# ESC.net
KiCad netlist of a schematic drawn in Altium Designer
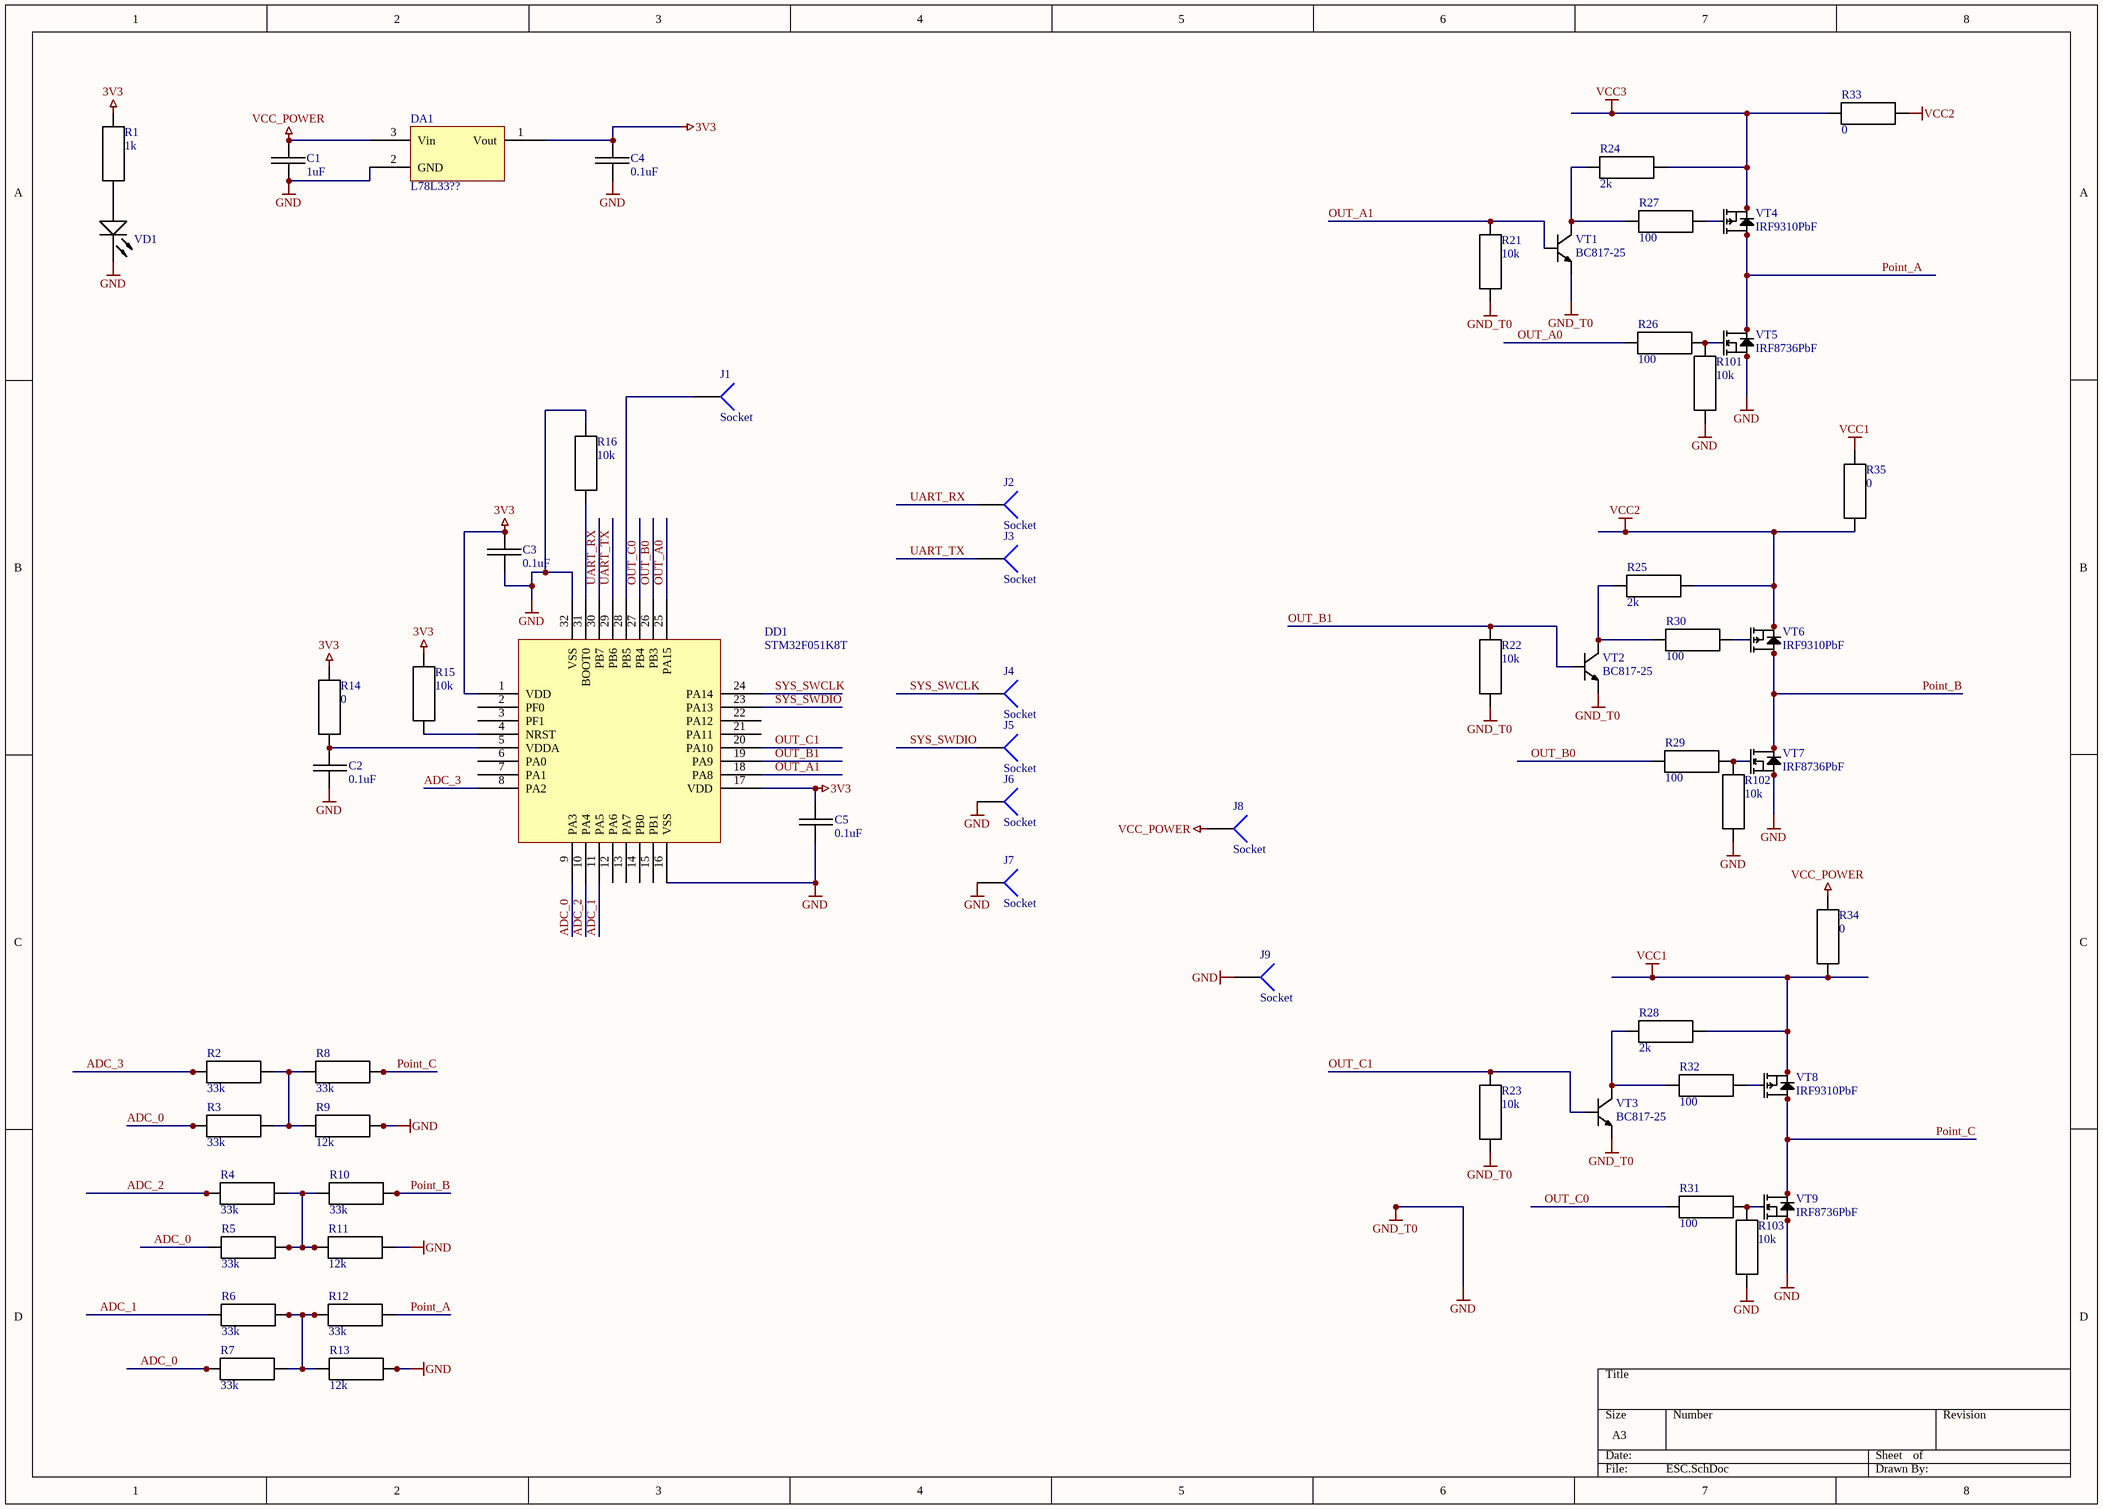
[diagram p0: ESC.SchDoc]

(export (version "E")
  (design (tool "Eeschema 10.0.6"))
  (components
    (comp (ref "C1")
      (value "1uF")
      (footprint "CAP0805")
      (fields (field (name "VOLTAGE") "50V"))
      (libsource (lib "Schlib1") (part "Capacitor"))
    )
    (comp (ref "C2")
      (value "0.1uF")
      (footprint "CAP0603")
      (fields (field (name "VOLTAGE") "50V"))
      (libsource (lib "Schlib1") (part "Capacitor"))
    )
    (comp (ref "C3")
      (value "0.1uF")
      (footprint "CAP0603")
      (fields (field (name "VOLTAGE") "50V"))
      (libsource (lib "Schlib1") (part "Capacitor"))
    )
    (comp (ref "C4")
      (value "0.1uF")
      (footprint "CAP0603")
      (fields (field (name "VOLTAGE") "50V"))
      (libsource (lib "Schlib1") (part "Capacitor"))
    )
    (comp (ref "C5")
      (value "0.1uF")
      (footprint "CAP0603")
      (fields (field (name "VOLTAGE") "50V"))
      (libsource (lib "Schlib1") (part "Capacitor"))
    )
    (comp (ref "DA1")
      (value "L78L33??")
      (footprint "SOT89")
      (description "LDO")
      (libsource (lib "Schlib1") (part "DA-L78L05"))
    )
    (comp (ref "DD1")
      (value "STM32F051K8T")
      (footprint "LQFP32-STM32")
      (description "LQFP32")
      (libsource (lib "Schlib1") (part "STM32F051K8T"))
    )
    (comp (ref "J1")
      (value "Socket")
      (footprint "PIN1")
      (fields (field (name "PUBLISHER") "Altium Limited"))
      (libsource (lib "Miscellaneous Connectors") (part "Socket"))
    )
    (comp (ref "J2")
      (value "Socket")
      (footprint "PIN1")
      (fields (field (name "PUBLISHER") "Altium Limited"))
      (libsource (lib "Miscellaneous Connectors") (part "Socket"))
    )
    (comp (ref "J3")
      (value "Socket")
      (footprint "PIN1")
      (fields (field (name "PUBLISHER") "Altium Limited"))
      (libsource (lib "Miscellaneous Connectors") (part "Socket"))
    )
    (comp (ref "J4")
      (value "Socket")
      (footprint "PIN1")
      (fields (field (name "PUBLISHER") "Altium Limited"))
      (libsource (lib "Miscellaneous Connectors") (part "Socket"))
    )
    (comp (ref "J5")
      (value "Socket")
      (footprint "PIN1")
      (fields (field (name "PUBLISHER") "Altium Limited"))
      (libsource (lib "Miscellaneous Connectors") (part "Socket"))
    )
    (comp (ref "J6")
      (value "Socket")
      (footprint "PIN1")
      (fields (field (name "PUBLISHER") "Altium Limited"))
      (libsource (lib "Miscellaneous Connectors") (part "Socket"))
    )
    (comp (ref "J7")
      (value "Socket")
      (footprint "PIN1")
      (fields (field (name "PUBLISHER") "Altium Limited"))
      (libsource (lib "Miscellaneous Connectors") (part "Socket"))
    )
    (comp (ref "J8")
      (value "Socket")
      (footprint "PIN1")
      (fields (field (name "PUBLISHER") "Altium Limited"))
      (libsource (lib "Miscellaneous Connectors") (part "Socket"))
    )
    (comp (ref "J9")
      (value "Socket")
      (footprint "PIN1")
      (fields (field (name "PUBLISHER") "Altium Limited"))
      (libsource (lib "Miscellaneous Connectors") (part "Socket"))
    )
    (comp (ref "R1") (value "1k") (footprint "RES0603") (libsource (lib "") (part "Resistor_2")))
    (comp (ref "R2") (value "33k") (footprint "RES0805") (libsource (lib "Schlib1") (part "Resistor")))
    (comp (ref "R3") (value "33k") (footprint "RES0805") (libsource (lib "Schlib1") (part "Resistor")))
    (comp (ref "R4") (value "33k") (footprint "RES0805") (libsource (lib "Schlib1") (part "Resistor")))
    (comp (ref "R5") (value "33k") (footprint "RES0805") (libsource (lib "Schlib1") (part "Resistor")))
    (comp (ref "R6") (value "33k") (footprint "RES0805") (libsource (lib "Schlib1") (part "Resistor")))
    (comp (ref "R7") (value "33k") (footprint "RES0805") (libsource (lib "Schlib1") (part "Resistor")))
    (comp (ref "R8") (value "33k") (footprint "RES0805") (libsource (lib "Schlib1") (part "Resistor")))
    (comp (ref "R9") (value "12k") (footprint "RES0805") (libsource (lib "Schlib1") (part "Resistor")))
    (comp (ref "R10") (value "33k") (footprint "RES0805") (libsource (lib "Schlib1") (part "Resistor")))
    (comp (ref "R11") (value "12k") (footprint "RES0805") (libsource (lib "Schlib1") (part "Resistor")))
    (comp (ref "R12") (value "33k") (footprint "RES0805") (libsource (lib "Schlib1") (part "Resistor")))
    (comp (ref "R13") (value "12k") (footprint "RES0805") (libsource (lib "Schlib1") (part "Resistor")))
    (comp (ref "R14") (value "0") (footprint "RES0603") (libsource (lib "") (part "Resistor_1")))
    (comp (ref "R15") (value "10k") (footprint "RES0603") (libsource (lib "") (part "Resistor_1")))
    (comp (ref "R16") (value "10k") (footprint "RES0603") (libsource (lib "") (part "Resistor_1")))
    (comp (ref "R21") (value "10k") (footprint "RES0603") (libsource (lib "") (part "Resistor_2")))
    (comp (ref "R22") (value "10k") (footprint "RES0603") (libsource (lib "") (part "Resistor_2")))
    (comp (ref "R23") (value "10k") (footprint "RES0603") (libsource (lib "") (part "Resistor_2")))
    (comp (ref "R24") (value "2k") (footprint "RES0603") (libsource (lib "Schlib1") (part "Resistor")))
    (comp (ref "R25") (value "2k") (footprint "RES0603") (libsource (lib "Schlib1") (part "Resistor")))
    (comp (ref "R26") (value "100") (footprint "RES0805") (libsource (lib "") (part "Resistor_3")))
    (comp (ref "R27") (value "100") (footprint "RES0603") (libsource (lib "") (part "Resistor_3")))
    (comp (ref "R28") (value "2k") (footprint "RES0603") (libsource (lib "Schlib1") (part "Resistor")))
    (comp (ref "R29") (value "100") (footprint "RES0805") (libsource (lib "") (part "Resistor_3")))
    (comp (ref "R30") (value "100") (footprint "RES0603") (libsource (lib "") (part "Resistor_3")))
    (comp (ref "R31") (value "100") (footprint "RES0805") (libsource (lib "") (part "Resistor_3")))
    (comp (ref "R32") (value "100") (footprint "RES0603") (libsource (lib "") (part "Resistor_3")))
    (comp (ref "R33") (value "0") (footprint "RES1206") (libsource (lib "") (part "Resistor_3")))
    (comp (ref "R34") (value "0") (footprint "RES2512") (libsource (lib "") (part "Resistor_1")))
    (comp (ref "R35") (value "0") (footprint "RES1206") (libsource (lib "") (part "Resistor_2")))
    (comp (ref "R101") (value "10k") (footprint "RES0603") (libsource (lib "") (part "Resistor_2")))
    (comp (ref "R102") (value "10k") (footprint "RES0603") (libsource (lib "") (part "Resistor_2")))
    (comp (ref "R103") (value "10k") (footprint "RES0603") (libsource (lib "") (part "Resistor_2")))
    (comp (ref "VD1")
      (value "KP-1608SURC")
      (footprint "Diode 1608")
      (libsource (lib "Schlib1") (part "LED_0603"))
    )
    (comp (ref "VT1")
      (value "BC817-25")
      (footprint "SOT23")
      (description "NPN")
      (libsource (lib "Schlib1") (part "VT - BC817"))
    )
    (comp (ref "VT2")
      (value "BC817-25")
      (footprint "SOT23")
      (description "NPN")
      (libsource (lib "Schlib1") (part "VT - BC817"))
    )
    (comp (ref "VT3")
      (value "BC817-25")
      (footprint "SOT23")
      (description "NPN")
      (libsource (lib "Schlib1") (part "VT - BC817"))
    )
    (comp (ref "VT4")
      (value "IRF9310PbF")
      (footprint "SO-8 IRF...")
      (description "P-MOSFET -20A")
      (libsource (lib "Schlib1") (part "IRF9310PbF"))
    )
    (comp (ref "VT5")
      (value "IRF8736PbF")
      (footprint "SO-8 IRF...")
      (description "N-MOSFET 18A")
      (libsource (lib "Schlib1") (part "IRF8736PbF"))
    )
    (comp (ref "VT6")
      (value "IRF9310PbF")
      (footprint "SO-8 IRF...")
      (description "P-MOSFET -20A")
      (libsource (lib "Schlib1") (part "IRF9310PbF"))
    )
    (comp (ref "VT7")
      (value "IRF8736PbF")
      (footprint "SO-8 IRF...")
      (description "N-MOSFET 18A")
      (libsource (lib "Schlib1") (part "IRF8736PbF"))
    )
    (comp (ref "VT8")
      (value "IRF9310PbF")
      (footprint "SO-8 IRF...")
      (description "P-MOSFET -20A")
      (libsource (lib "Schlib1") (part "IRF9310PbF"))
    )
    (comp (ref "VT9")
      (value "IRF8736PbF")
      (footprint "SO-8 IRF...")
      (description "N-MOSFET 18A")
      (libsource (lib "Schlib1") (part "IRF8736PbF"))
    )
  )
  (nets
    (net (code "1") (name "/ADC_0") (class "Default")
      (node (ref "DD1") (pin "9") (pinfunction "PA3_9") (pintype "passive"))
      (node (ref "R3") (pin "2") (pinfunction "2_2") (pintype "passive"))
      (node (ref "R5") (pin "2") (pinfunction "2_2") (pintype "passive"))
      (node (ref "R7") (pin "2") (pinfunction "2_2") (pintype "passive"))
    )
    (net (code "2") (name "/ADC_1") (class "Default")
      (node (ref "DD1") (pin "11") (pinfunction "PA5_11") (pintype "passive"))
      (node (ref "R6") (pin "2") (pinfunction "2_2") (pintype "passive"))
    )
    (net (code "3") (name "/ADC_2") (class "Default")
      (node (ref "DD1") (pin "10") (pinfunction "PA4_10") (pintype "passive"))
      (node (ref "R4") (pin "2") (pinfunction "2_2") (pintype "passive"))
    )
    (net (code "4") (name "/ADC_3") (class "Default")
      (node (ref "DD1") (pin "8") (pinfunction "PA2_8") (pintype "passive"))
      (node (ref "R2") (pin "2") (pinfunction "2_2") (pintype "passive"))
    )
    (net (code "5") (name "/OUT_A0") (class "Default")
      (node (ref "DD1") (pin "25") (pinfunction "PA15_25") (pintype "passive"))
      (node (ref "R26") (pin "1") (pinfunction "1_1") (pintype "passive"))
    )
    (net (code "6") (name "/OUT_A1") (class "Default")
      (node (ref "DD1") (pin "18") (pinfunction "PA8_18") (pintype "passive"))
      (node (ref "R21") (pin "1") (pinfunction "1_1") (pintype "passive"))
      (node (ref "VT1") (pin "1") (pinfunction "1_1") (pintype "passive"))
    )
    (net (code "7") (name "/OUT_B0") (class "Default")
      (node (ref "DD1") (pin "26") (pinfunction "PB3_26") (pintype "passive"))
      (node (ref "R29") (pin "1") (pinfunction "1_1") (pintype "passive"))
    )
    (net (code "8") (name "/OUT_B1") (class "Default")
      (node (ref "DD1") (pin "19") (pinfunction "PA9_19") (pintype "passive"))
      (node (ref "R22") (pin "1") (pinfunction "1_1") (pintype "passive"))
      (node (ref "VT2") (pin "1") (pinfunction "1_1") (pintype "passive"))
    )
    (net (code "9") (name "/OUT_C0") (class "Default")
      (node (ref "DD1") (pin "27") (pinfunction "PB4_27") (pintype "passive"))
      (node (ref "R31") (pin "1") (pinfunction "1_1") (pintype "passive"))
    )
    (net (code "10") (name "/OUT_C1") (class "Default")
      (node (ref "DD1") (pin "20") (pinfunction "PA10_20") (pintype "passive"))
      (node (ref "R23") (pin "1") (pinfunction "1_1") (pintype "passive"))
      (node (ref "VT3") (pin "1") (pinfunction "1_1") (pintype "passive"))
    )
    (net (code "11") (name "/Point_A") (class "Default")
      (node (ref "R12") (pin "1") (pinfunction "1_1") (pintype "passive"))
      (node (ref "VT4") (pin "5") (pinfunction "D_5") (pintype "passive"))
      (node (ref "VT4") (pin "6") (pinfunction "D_6") (pintype "passive"))
      (node (ref "VT4") (pin "7") (pinfunction "D_7") (pintype "passive"))
      (node (ref "VT4") (pin "8") (pinfunction "D_8") (pintype "passive"))
      (node (ref "VT5") (pin "5") (pinfunction "D_5") (pintype "passive"))
      (node (ref "VT5") (pin "6") (pinfunction "D_6") (pintype "passive"))
      (node (ref "VT5") (pin "7") (pinfunction "D_7") (pintype "passive"))
      (node (ref "VT5") (pin "8") (pinfunction "D_8") (pintype "passive"))
    )
    (net (code "12") (name "/Point_B") (class "Default")
      (node (ref "R10") (pin "1") (pinfunction "1_1") (pintype "passive"))
      (node (ref "VT6") (pin "5") (pinfunction "D_5") (pintype "passive"))
      (node (ref "VT6") (pin "6") (pinfunction "D_6") (pintype "passive"))
      (node (ref "VT6") (pin "7") (pinfunction "D_7") (pintype "passive"))
      (node (ref "VT6") (pin "8") (pinfunction "D_8") (pintype "passive"))
      (node (ref "VT7") (pin "5") (pinfunction "D_5") (pintype "passive"))
      (node (ref "VT7") (pin "6") (pinfunction "D_6") (pintype "passive"))
      (node (ref "VT7") (pin "7") (pinfunction "D_7") (pintype "passive"))
      (node (ref "VT7") (pin "8") (pinfunction "D_8") (pintype "passive"))
    )
    (net (code "13") (name "/Point_C") (class "Default")
      (node (ref "R8") (pin "1") (pinfunction "1_1") (pintype "passive"))
      (node (ref "VT8") (pin "5") (pinfunction "D_5") (pintype "passive"))
      (node (ref "VT8") (pin "6") (pinfunction "D_6") (pintype "passive"))
      (node (ref "VT8") (pin "7") (pinfunction "D_7") (pintype "passive"))
      (node (ref "VT8") (pin "8") (pinfunction "D_8") (pintype "passive"))
      (node (ref "VT9") (pin "5") (pinfunction "D_5") (pintype "passive"))
      (node (ref "VT9") (pin "6") (pinfunction "D_6") (pintype "passive"))
      (node (ref "VT9") (pin "7") (pinfunction "D_7") (pintype "passive"))
      (node (ref "VT9") (pin "8") (pinfunction "D_8") (pintype "passive"))
    )
    (net (code "14") (name "/SYS_SWCLK") (class "Default")
      (node (ref "DD1") (pin "24") (pinfunction "PA14_24") (pintype "passive"))
      (node (ref "J4") (pin "1") (pinfunction "1_1") (pintype "passive"))
    )
    (net (code "15") (name "/SYS_SWDIO") (class "Default")
      (node (ref "DD1") (pin "23") (pinfunction "PA13_23") (pintype "passive"))
      (node (ref "J5") (pin "1") (pinfunction "1_1") (pintype "passive"))
    )
    (net (code "16") (name "/UART_RX") (class "Default")
      (node (ref "DD1") (pin "30") (pinfunction "PB7_30") (pintype "passive"))
      (node (ref "J2") (pin "1") (pinfunction "1_1") (pintype "passive"))
    )
    (net (code "17") (name "/UART_TX") (class "Default")
      (node (ref "DD1") (pin "29") (pinfunction "PB6_29") (pintype "passive"))
      (node (ref "J3") (pin "1") (pinfunction "1_1") (pintype "passive"))
    )
    (net (code "18") (name "3V3") (class "Default")
      (node (ref "C3") (pin "1") (pinfunction "1_1") (pintype "passive"))
      (node (ref "C4") (pin "1") (pinfunction "1_1") (pintype "passive"))
      (node (ref "C5") (pin "2") (pinfunction "2_2") (pintype "passive"))
      (node (ref "DA1") (pin "1") (pinfunction "Vout_1") (pintype "passive"))
      (node (ref "DD1") (pin "1") (pinfunction "VDD_1") (pintype "passive"))
      (node (ref "DD1") (pin "17") (pinfunction "VDD_17") (pintype "passive"))
      (node (ref "R1") (pin "1") (pinfunction "1_1") (pintype "passive"))
      (node (ref "R14") (pin "2") (pinfunction "2_2") (pintype "passive"))
      (node (ref "R15") (pin "2") (pinfunction "2_2") (pintype "passive"))
    )
    (net (code "19") (name "GND") (class "Default")
      (node (ref "C1") (pin "2") (pinfunction "2_2") (pintype "passive"))
      (node (ref "C2") (pin "1") (pinfunction "1_1") (pintype "passive"))
      (node (ref "C3") (pin "2") (pinfunction "2_2") (pintype "passive"))
      (node (ref "C4") (pin "2") (pinfunction "2_2") (pintype "passive"))
      (node (ref "C5") (pin "1") (pinfunction "1_1") (pintype "passive"))
      (node (ref "DA1") (pin "2") (pinfunction "GND_2") (pintype "passive"))
      (node (ref "DD1") (pin "16") (pinfunction "VSS_16") (pintype "passive"))
      (node (ref "DD1") (pin "32") (pinfunction "VSS_32") (pintype "passive"))
      (node (ref "J6") (pin "1") (pinfunction "1_1") (pintype "passive"))
      (node (ref "J7") (pin "1") (pinfunction "1_1") (pintype "passive"))
      (node (ref "J9") (pin "1") (pinfunction "1_1") (pintype "passive"))
      (node (ref "R101") (pin "2") (pinfunction "2_2") (pintype "passive"))
      (node (ref "R102") (pin "2") (pinfunction "2_2") (pintype "passive"))
      (node (ref "R103") (pin "2") (pinfunction "2_2") (pintype "passive"))
      (node (ref "R11") (pin "1") (pinfunction "1_1") (pintype "passive"))
      (node (ref "R13") (pin "1") (pinfunction "1_1") (pintype "passive"))
      (node (ref "R16") (pin "2") (pinfunction "2_2") (pintype "passive"))
      (node (ref "R21") (pin "2") (pinfunction "2_2") (pintype "passive"))
      (node (ref "R22") (pin "2") (pinfunction "2_2") (pintype "passive"))
      (node (ref "R23") (pin "2") (pinfunction "2_2") (pintype "passive"))
      (node (ref "R9") (pin "1") (pinfunction "1_1") (pintype "passive"))
      (node (ref "VD1") (pin "1") (pinfunction "1_1") (pintype "passive"))
      (node (ref "VT1") (pin "2") (pinfunction "2_2") (pintype "passive"))
      (node (ref "VT2") (pin "2") (pinfunction "2_2") (pintype "passive"))
      (node (ref "VT3") (pin "2") (pinfunction "2_2") (pintype "passive"))
      (node (ref "VT5") (pin "1") (pinfunction "S_1") (pintype "passive"))
      (node (ref "VT5") (pin "2") (pinfunction "S_2") (pintype "passive"))
      (node (ref "VT5") (pin "3") (pinfunction "S_3") (pintype "passive"))
      (node (ref "VT7") (pin "1") (pinfunction "S_1") (pintype "passive"))
      (node (ref "VT7") (pin "2") (pinfunction "S_2") (pintype "passive"))
      (node (ref "VT7") (pin "3") (pinfunction "S_3") (pintype "passive"))
      (node (ref "VT9") (pin "1") (pinfunction "S_1") (pintype "passive"))
      (node (ref "VT9") (pin "2") (pinfunction "S_2") (pintype "passive"))
      (node (ref "VT9") (pin "3") (pinfunction "S_3") (pintype "passive"))
    )
    (net (code "20") (name "Net-(DD1-BOOT0)") (class "Default")
      (node (ref "DD1") (pin "31") (pinfunction "BOOT0_31") (pintype "passive"))
      (node (ref "R16") (pin "1") (pinfunction "1_1") (pintype "passive"))
    )
    (net (code "21") (name "Net-(DD1-NRST)") (class "Default")
      (node (ref "DD1") (pin "4") (pinfunction "NRST_4") (pintype "passive"))
      (node (ref "R15") (pin "1") (pinfunction "1_1") (pintype "passive"))
    )
    (net (code "22") (name "Net-(DD1-PB5)") (class "Default")
      (node (ref "DD1") (pin "28") (pinfunction "PB5_28") (pintype "passive"))
      (node (ref "J1") (pin "1") (pinfunction "1_1") (pintype "passive"))
    )
    (net (code "23") (name "Net-(DD1-VDDA)") (class "Default")
      (node (ref "C2") (pin "2") (pinfunction "2_2") (pintype "passive"))
      (node (ref "DD1") (pin "5") (pinfunction "VDDA_5") (pintype "passive"))
      (node (ref "R14") (pin "1") (pinfunction "1_1") (pintype "passive"))
    )
    (net (code "24") (name "Net-(R1-Pad2)") (class "Default")
      (node (ref "R1") (pin "2") (pinfunction "2_2") (pintype "passive"))
      (node (ref "VD1") (pin "2") (pinfunction "2_2") (pintype "passive"))
    )
    (net (code "25") (name "Net-(R2-Pad1)") (class "Default")
      (node (ref "R2") (pin "1") (pinfunction "1_1") (pintype "passive"))
      (node (ref "R3") (pin "1") (pinfunction "1_1") (pintype "passive"))
      (node (ref "R8") (pin "2") (pinfunction "2_2") (pintype "passive"))
      (node (ref "R9") (pin "2") (pinfunction "2_2") (pintype "passive"))
    )
    (net (code "26") (name "Net-(R10-Pad2)") (class "Default")
      (node (ref "R10") (pin "2") (pinfunction "2_2") (pintype "passive"))
      (node (ref "R11") (pin "2") (pinfunction "2_2") (pintype "passive"))
      (node (ref "R4") (pin "1") (pinfunction "1_1") (pintype "passive"))
      (node (ref "R5") (pin "1") (pinfunction "1_1") (pintype "passive"))
    )
    (net (code "27") (name "Net-(R12-Pad2)") (class "Default")
      (node (ref "R12") (pin "2") (pinfunction "2_2") (pintype "passive"))
      (node (ref "R13") (pin "2") (pinfunction "2_2") (pintype "passive"))
      (node (ref "R6") (pin "1") (pinfunction "1_1") (pintype "passive"))
      (node (ref "R7") (pin "1") (pinfunction "1_1") (pintype "passive"))
    )
    (net (code "28") (name "Net-(R24-Pad2)") (class "Default")
      (node (ref "R24") (pin "2") (pinfunction "2_2") (pintype "passive"))
      (node (ref "R27") (pin "1") (pinfunction "1_1") (pintype "passive"))
      (node (ref "VT1") (pin "3") (pinfunction "3_3") (pintype "passive"))
    )
    (net (code "29") (name "Net-(R25-Pad2)") (class "Default")
      (node (ref "R25") (pin "2") (pinfunction "2_2") (pintype "passive"))
      (node (ref "R30") (pin "1") (pinfunction "1_1") (pintype "passive"))
      (node (ref "VT2") (pin "3") (pinfunction "3_3") (pintype "passive"))
    )
    (net (code "30") (name "Net-(R28-Pad2)") (class "Default")
      (node (ref "R28") (pin "2") (pinfunction "2_2") (pintype "passive"))
      (node (ref "R32") (pin "1") (pinfunction "1_1") (pintype "passive"))
      (node (ref "VT3") (pin "3") (pinfunction "3_3") (pintype "passive"))
    )
    (net (code "31") (name "Net-(VT4-G)") (class "Default")
      (node (ref "R27") (pin "2") (pinfunction "2_2") (pintype "passive"))
      (node (ref "VT4") (pin "4") (pinfunction "G_4") (pintype "passive"))
    )
    (net (code "32") (name "Net-(VT5-G)") (class "Default")
      (node (ref "R101") (pin "1") (pinfunction "1_1") (pintype "passive"))
      (node (ref "R26") (pin "2") (pinfunction "2_2") (pintype "passive"))
      (node (ref "VT5") (pin "4") (pinfunction "G_4") (pintype "passive"))
    )
    (net (code "33") (name "Net-(VT6-G)") (class "Default")
      (node (ref "R30") (pin "2") (pinfunction "2_2") (pintype "passive"))
      (node (ref "VT6") (pin "4") (pinfunction "G_4") (pintype "passive"))
    )
    (net (code "34") (name "Net-(VT7-G)") (class "Default")
      (node (ref "R102") (pin "1") (pinfunction "1_1") (pintype "passive"))
      (node (ref "R29") (pin "2") (pinfunction "2_2") (pintype "passive"))
      (node (ref "VT7") (pin "4") (pinfunction "G_4") (pintype "passive"))
    )
    (net (code "35") (name "Net-(VT8-G)") (class "Default")
      (node (ref "R32") (pin "2") (pinfunction "2_2") (pintype "passive"))
      (node (ref "VT8") (pin "4") (pinfunction "G_4") (pintype "passive"))
    )
    (net (code "36") (name "Net-(VT9-G)") (class "Default")
      (node (ref "R103") (pin "1") (pinfunction "1_1") (pintype "passive"))
      (node (ref "R31") (pin "2") (pinfunction "2_2") (pintype "passive"))
      (node (ref "VT9") (pin "4") (pinfunction "G_4") (pintype "passive"))
    )
    (net (code "37") (name "VCC1") (class "Default")
      (node (ref "R28") (pin "1") (pinfunction "1_1") (pintype "passive"))
      (node (ref "R34") (pin "1") (pinfunction "1_1") (pintype "passive"))
      (node (ref "R35") (pin "1") (pinfunction "1_1") (pintype "passive"))
      (node (ref "VT8") (pin "1") (pinfunction "S_1") (pintype "passive"))
      (node (ref "VT8") (pin "2") (pinfunction "S_2") (pintype "passive"))
      (node (ref "VT8") (pin "3") (pinfunction "S_3") (pintype "passive"))
    )
    (net (code "38") (name "VCC2") (class "Default")
      (node (ref "R25") (pin "1") (pinfunction "1_1") (pintype "passive"))
      (node (ref "R33") (pin "2") (pinfunction "2_2") (pintype "passive"))
      (node (ref "R35") (pin "2") (pinfunction "2_2") (pintype "passive"))
      (node (ref "VT6") (pin "1") (pinfunction "S_1") (pintype "passive"))
      (node (ref "VT6") (pin "2") (pinfunction "S_2") (pintype "passive"))
      (node (ref "VT6") (pin "3") (pinfunction "S_3") (pintype "passive"))
    )
    (net (code "39") (name "VCC3") (class "Default")
      (node (ref "R24") (pin "1") (pinfunction "1_1") (pintype "passive"))
      (node (ref "R33") (pin "1") (pinfunction "1_1") (pintype "passive"))
      (node (ref "VT4") (pin "1") (pinfunction "S_1") (pintype "passive"))
      (node (ref "VT4") (pin "2") (pinfunction "S_2") (pintype "passive"))
      (node (ref "VT4") (pin "3") (pinfunction "S_3") (pintype "passive"))
    )
    (net (code "40") (name "VCC_POWER") (class "Default")
      (node (ref "C1") (pin "1") (pinfunction "1_1") (pintype "passive"))
      (node (ref "DA1") (pin "3") (pinfunction "Vin_3") (pintype "passive"))
      (node (ref "J8") (pin "1") (pinfunction "1_1") (pintype "passive"))
      (node (ref "R34") (pin "2") (pinfunction "2_2") (pintype "passive"))
    )
    (net (code "41") (name "unconnected-(DD1-PA0-Pad6)") (class "Default")
      (node (ref "DD1") (pin "6") (pinfunction "PA0_6") (pintype "passive"))
    )
    (net (code "42") (name "unconnected-(DD1-PA1-Pad7)") (class "Default")
      (node (ref "DD1") (pin "7") (pinfunction "PA1_7") (pintype "passive"))
    )
    (net (code "43") (name "unconnected-(DD1-PA6-Pad12)") (class "Default")
      (node (ref "DD1") (pin "12") (pinfunction "PA6_12") (pintype "passive"))
    )
    (net (code "44") (name "unconnected-(DD1-PA7-Pad13)") (class "Default")
      (node (ref "DD1") (pin "13") (pinfunction "PA7_13") (pintype "passive"))
    )
    (net (code "45") (name "unconnected-(DD1-PA11-Pad21)") (class "Default")
      (node (ref "DD1") (pin "21") (pinfunction "PA11_21") (pintype "passive"))
    )
    (net (code "46") (name "unconnected-(DD1-PA12-Pad22)") (class "Default")
      (node (ref "DD1") (pin "22") (pinfunction "PA12_22") (pintype "passive"))
    )
    (net (code "47") (name "unconnected-(DD1-PB0-Pad14)") (class "Default")
      (node (ref "DD1") (pin "14") (pinfunction "PB0_14") (pintype "passive"))
    )
    (net (code "48") (name "unconnected-(DD1-PB1-Pad15)") (class "Default")
      (node (ref "DD1") (pin "15") (pinfunction "PB1_15") (pintype "passive"))
    )
    (net (code "49") (name "unconnected-(DD1-PF0-Pad2)") (class "Default")
      (node (ref "DD1") (pin "2") (pinfunction "PF0_2") (pintype "passive"))
    )
    (net (code "50") (name "unconnected-(DD1-PF1-Pad3)") (class "Default")
      (node (ref "DD1") (pin "3") (pinfunction "PF1_3") (pintype "passive"))
    )
  )
)
